# final_schematic.net
KiCad netlist of a schematic drawn in EAGLE
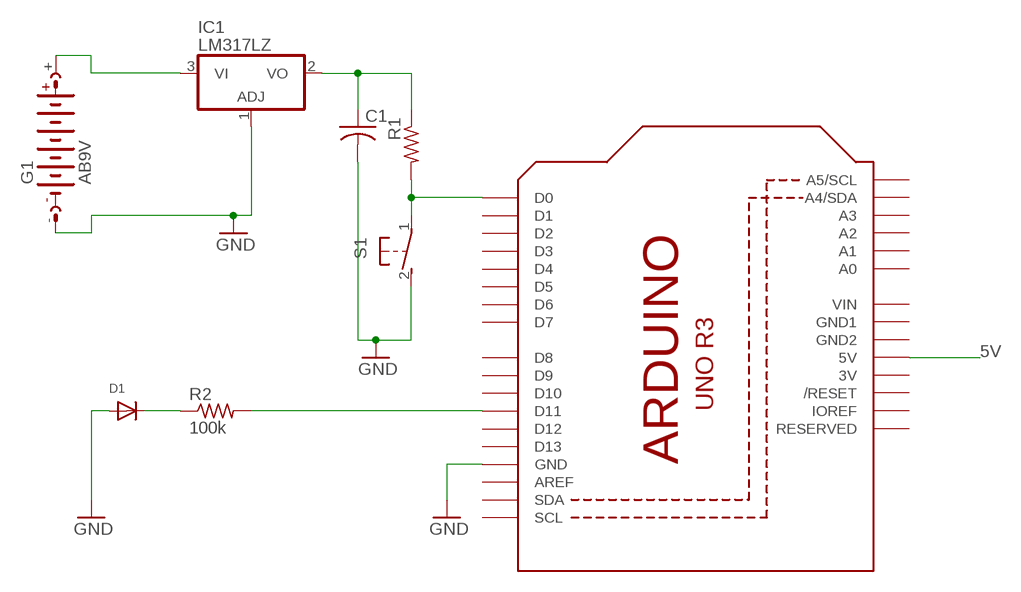
[diagram p0: schematic, sheet 1]

(export (version "E")
  (design (tool "Eeschema 10.0.6"))
  (components
    (comp (ref "C1")
      (value "C-USC0805")
      (footprint "eagle-import:C0805")
      (libsource (lib "eagle-import") (part "C-USC0805"))
    )
    (comp (ref "D1")
      (value "DIODEDO-1N4148")
      (footprint "eagle-import:DO-1N4148")
      (libsource (lib "eagle-import") (part "DIODEDO-1N4148"))
    )
    (comp (ref "G1")
      (value "AB9V")
      (footprint "eagle-import:AB9V")
      (libsource (lib "eagle-import") (part "AB9V"))
    )
    (comp (ref "IC1")
      (value "LM317LZ")
      (footprint "eagle-import:TO92")
      (libsource (lib "eagle-import") (part "317LZLM"))
    )
    (comp (ref "R1")
      (value "R-US_M0805")
      (footprint "eagle-import:M0805")
      (libsource (lib "eagle-import") (part "R-US_M0805"))
    )
    (comp (ref "R2")
      (value "100k")
      (footprint "eagle-import:R0805")
      (libsource (lib "eagle-import") (part "R-US_R0805"))
    )
    (comp (ref "S1")
      (value "31-XX")
      (footprint "eagle-import:B3F-31XX")
      (libsource (lib "eagle-import") (part "31-XX"))
    )
    (comp (ref "U1")
      (value "ARDUINOR3-DIMENSION")
      (footprint "eagle-import:ARDUINOR3")
      (libsource (lib "eagle-import") (part "ARDUINOR3-DIMENSION"))
    )
  )
  (nets
    (net (code "1") (name "/3V") (class "Default")
      (node (ref "U1") (pin "3V") (pinfunction "3V_3V") (pintype "power_in"))
    )
    (net (code "2") (name "/5V") (class "Default")
      (node (ref "U1") (pin "5V") (pinfunction "5V_5V") (pintype "power_in"))
    )
    (net (code "3") (name "/GND1") (class "Default")
      (node (ref "U1") (pin "GND1") (pinfunction "GND1_GND1") (pintype "power_in"))
    )
    (net (code "4") (name "/GND2") (class "Default")
      (node (ref "U1") (pin "GND2") (pinfunction "GND2_GND2") (pintype "power_in"))
    )
    (net (code "5") (name "/VIN") (class "Default")
      (node (ref "U1") (pin "VIN") (pinfunction "VIN_VIN") (pintype "power_in"))
    )
    (net (code "6") (name "GND") (class "Default")
      (node (ref "C1") (pin "2") (pinfunction "2_2") (pintype "passive"))
      (node (ref "D1") (pin "A") (pinfunction "A_A") (pintype "passive"))
      (node (ref "G1") (pin "-") (pinfunction "-_-") (pintype "passive"))
      (node (ref "IC1") (pin "1") (pinfunction "ADJ_1") (pintype "input"))
      (node (ref "S1") (pin "2") (pinfunction "S_2") (pintype "passive"))
      (node (ref "U1") (pin "GND") (pinfunction "GND_GND") (pintype "power_in"))
    )
    (net (code "7") (name "Net-(D1-PadC)") (class "Default")
      (node (ref "D1") (pin "C") (pinfunction "C_C") (pintype "passive"))
      (node (ref "R2") (pin "1") (pinfunction "1_1") (pintype "passive"))
    )
    (net (code "8") (name "Net-(IC1-VI)") (class "Default")
      (node (ref "G1") (pin "+") (pinfunction "+_+") (pintype "passive"))
      (node (ref "IC1") (pin "3") (pinfunction "VI_3") (pintype "input"))
    )
    (net (code "9") (name "Net-(IC1-VO)") (class "Default")
      (node (ref "C1") (pin "1") (pinfunction "1_1") (pintype "passive"))
      (node (ref "IC1") (pin "2") (pinfunction "VO_2") (pintype "passive"))
      (node (ref "R1") (pin "1") (pinfunction "1_1") (pintype "passive"))
    )
    (net (code "10") (name "Net-(R2-Pad2)") (class "Default")
      (node (ref "R2") (pin "2") (pinfunction "2_2") (pintype "passive"))
      (node (ref "U1") (pin "D11") (pinfunction "D11_D11") (pintype "bidirectional"))
    )
    (net (code "11") (name "Net-(S1-P)") (class "Default")
      (node (ref "R1") (pin "2") (pinfunction "2_2") (pintype "passive"))
      (node (ref "S1") (pin "1") (pinfunction "P_1") (pintype "passive"))
      (node (ref "U1") (pin "D0") (pinfunction "D0_D0") (pintype "bidirectional"))
    )
    (net (code "12") (name "unconnected-(U1-A4{slash}SDA-PadA4)") (class "Default")
      (node (ref "U1") (pin "A4") (pinfunction "A4/SDA_A4") (pintype "bidirectional"))
    )
    (net (code "13") (name "unconnected-(U1-A5{slash}SCL-PadA5)") (class "Default")
      (node (ref "U1") (pin "A5") (pinfunction "A5/SCL_A5") (pintype "bidirectional"))
    )
    (net (code "14") (name "unconnected-(U1-PadA0)") (class "Default")
      (node (ref "U1") (pin "A0") (pinfunction "A0_A0") (pintype "bidirectional"))
    )
    (net (code "15") (name "unconnected-(U1-PadA1)") (class "Default")
      (node (ref "U1") (pin "A1") (pinfunction "A1_A1") (pintype "bidirectional"))
    )
    (net (code "16") (name "unconnected-(U1-PadA2)") (class "Default")
      (node (ref "U1") (pin "A2") (pinfunction "A2_A2") (pintype "bidirectional"))
    )
    (net (code "17") (name "unconnected-(U1-PadA3)") (class "Default")
      (node (ref "U1") (pin "A3") (pinfunction "A3_A3") (pintype "bidirectional"))
    )
    (net (code "18") (name "unconnected-(U1-PadAREF)") (class "Default")
      (node (ref "U1") (pin "AREF") (pinfunction "AREF_AREF") (pintype "bidirectional"))
    )
    (net (code "19") (name "unconnected-(U1-PadD1)") (class "Default")
      (node (ref "U1") (pin "D1") (pinfunction "D1_D1") (pintype "bidirectional"))
    )
    (net (code "20") (name "unconnected-(U1-PadD2)") (class "Default")
      (node (ref "U1") (pin "D2") (pinfunction "D2_D2") (pintype "bidirectional"))
    )
    (net (code "21") (name "unconnected-(U1-PadD3)") (class "Default")
      (node (ref "U1") (pin "D3") (pinfunction "D3_D3") (pintype "bidirectional"))
    )
    (net (code "22") (name "unconnected-(U1-PadD4)") (class "Default")
      (node (ref "U1") (pin "D4") (pinfunction "D4_D4") (pintype "bidirectional"))
    )
    (net (code "23") (name "unconnected-(U1-PadD5)") (class "Default")
      (node (ref "U1") (pin "D5") (pinfunction "D5_D5") (pintype "bidirectional"))
    )
    (net (code "24") (name "unconnected-(U1-PadD6)") (class "Default")
      (node (ref "U1") (pin "D6") (pinfunction "D6_D6") (pintype "bidirectional"))
    )
    (net (code "25") (name "unconnected-(U1-PadD7)") (class "Default")
      (node (ref "U1") (pin "D7") (pinfunction "D7_D7") (pintype "bidirectional"))
    )
    (net (code "26") (name "unconnected-(U1-PadD8)") (class "Default")
      (node (ref "U1") (pin "D8") (pinfunction "D8_D8") (pintype "bidirectional"))
    )
    (net (code "27") (name "unconnected-(U1-PadD9)") (class "Default")
      (node (ref "U1") (pin "D9") (pinfunction "D9_D9") (pintype "bidirectional"))
    )
    (net (code "28") (name "unconnected-(U1-PadD10)") (class "Default")
      (node (ref "U1") (pin "D10") (pinfunction "D10_D10") (pintype "bidirectional"))
    )
    (net (code "29") (name "unconnected-(U1-PadD12)") (class "Default")
      (node (ref "U1") (pin "D12") (pinfunction "D12_D12") (pintype "bidirectional"))
    )
    (net (code "30") (name "unconnected-(U1-PadD13)") (class "Default")
      (node (ref "U1") (pin "D13") (pinfunction "D13_D13") (pintype "bidirectional"))
    )
    (net (code "31") (name "unconnected-(U1-PadIOREF)") (class "Default")
      (node (ref "U1") (pin "IOREF") (pinfunction "IOREF_IOREF") (pintype "output"))
    )
    (net (code "32") (name "unconnected-(U1-PadRESERVED)") (class "Default")
      (node (ref "U1") (pin "RESERVED") (pinfunction "RESERVED_RESERVED") (pintype "no_connect"))
    )
    (net (code "33") (name "unconnected-(U1-PadSCL)") (class "Default")
      (node (ref "U1") (pin "SCL") (pinfunction "SCL_SCL") (pintype "bidirectional"))
    )
    (net (code "34") (name "unconnected-(U1-PadSDA)") (class "Default")
      (node (ref "U1") (pin "SDA") (pinfunction "SDA_SDA") (pintype "bidirectional"))
    )
    (net (code "35") (name "unconnected-(U1-{slash}RESET-PadRESET)") (class "Default")
      (node (ref "U1") (pin "RESET") (pinfunction "/RESET_RESET") (pintype "bidirectional"))
    )
  )
)
